# pwr.net
KiCad netlist of a schematic drawn in Altium Designer
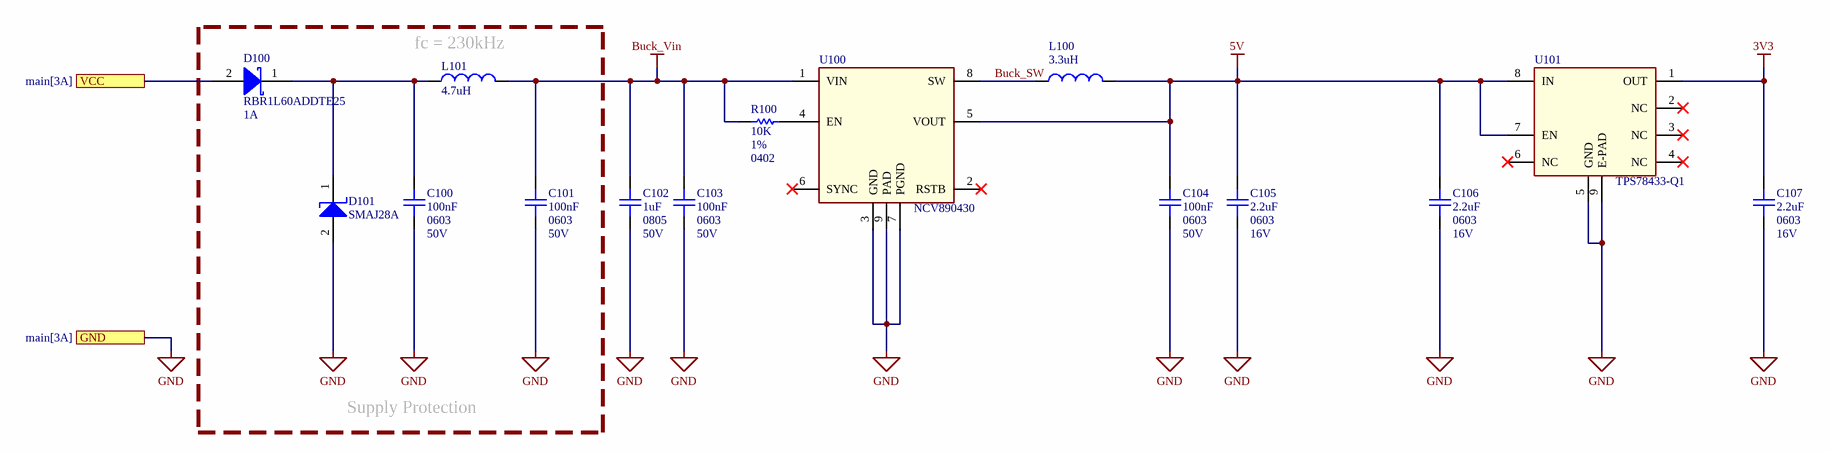
[diagram p0: pwr.SchDoc]

(export (version "E")
  (design (tool "Eeschema 10.0.6"))
  (components
    (comp (ref "C100")
      (value "100nF")
      (footprint "CER0603")
      (description "MLCC Automotive, 100nF, 0603, 50V, 10%, X8L")
      (fields
        (field (name "CASE/PACKAGE") "0603")
        (field (name "OP VOLTAGE") "50V")
        (field (name "TOLERANCE") "10%")
      )
      (libsource (lib "PMP_CapsDB") (part "CapCer_SMD_2"))
    )
    (comp (ref "C101")
      (value "100nF")
      (footprint "CER0603")
      (description "MLCC Automotive, 100nF, 0603, 50V, 10%, X8L")
      (fields
        (field (name "CASE/PACKAGE") "0603")
        (field (name "OP VOLTAGE") "50V")
        (field (name "TOLERANCE") "10%")
      )
      (libsource (lib "PMP_CapsDB") (part "CapCer_SMD_2"))
    )
    (comp (ref "C102")
      (value "1uF")
      (footprint "CER0805")
      (description "MLCC Automotive, 1uF, 0805, 50V, 10%, X7R")
      (fields
        (field (name "CASE/PACKAGE") "0805")
        (field (name "OP VOLTAGE") "50V")
        (field (name "TOLERANCE") "10%")
      )
      (libsource (lib "PMP_CapsDB") (part "CapCer_SMD_2"))
    )
    (comp (ref "C103")
      (value "100nF")
      (footprint "CER0603")
      (description "MLCC Automotive, 100nF, 0603, 50V, 10%, X8L")
      (fields
        (field (name "CASE/PACKAGE") "0603")
        (field (name "OP VOLTAGE") "50V")
        (field (name "TOLERANCE") "10%")
      )
      (libsource (lib "PMP_CapsDB") (part "CapCer_SMD_2"))
    )
    (comp (ref "C104")
      (value "100nF")
      (footprint "CER0603")
      (description "MLCC Automotive, 100nF, 0603, 50V, 10%, X8L")
      (fields
        (field (name "CASE/PACKAGE") "0603")
        (field (name "OP VOLTAGE") "50V")
        (field (name "TOLERANCE") "10%")
      )
      (libsource (lib "PMP_CapsDB") (part "CapCer_SMD_2"))
    )
    (comp (ref "C105")
      (value "2.2uF")
      (footprint "CER0603")
      (description "MLCC Automotive, 2.2uF, 0603, 16V, 10%, X7S")
      (fields
        (field (name "CASE/PACKAGE") "0603")
        (field (name "OP VOLTAGE") "16V")
        (field (name "TOLERANCE") "10%")
      )
      (libsource (lib "PMP_CapsDB") (part "CapCer_SMD_2"))
    )
    (comp (ref "C106")
      (value "2.2uF")
      (footprint "CER0603")
      (description "MLCC Automotive, 2.2uF, 0603, 16V, 10%, X7S")
      (fields
        (field (name "CASE/PACKAGE") "0603")
        (field (name "OP VOLTAGE") "16V")
        (field (name "TOLERANCE") "10%")
      )
      (libsource (lib "PMP_CapsDB") (part "CapCer_SMD_2"))
    )
    (comp (ref "C107")
      (value "2.2uF")
      (footprint "CER0603")
      (description "MLCC Automotive, 2.2uF, 0603, 16V, 10%, X7S")
      (fields
        (field (name "CASE/PACKAGE") "0603")
        (field (name "OP VOLTAGE") "16V")
        (field (name "TOLERANCE") "10%")
      )
      (libsource (lib "PMP_CapsDB") (part "CapCer_SMD_2"))
    )
    (comp (ref "D100")
      (value "RBR1L60ADDTE25")
      (footprint "DO-214AC_SMA")
      (description "Schottky Rectifier Diode 1A 60V SMA")
      (fields (field (name "IF (A)") "1A") (field (name "Comment") "Shottky Rect Diode SMD"))
      (libsource (lib "Pmp_DiscretesDB") (part "Diode_SMD_2_Schottky"))
    )
    (comp (ref "D101")
      (value "SMAJ28A")
      (footprint "DO-214AC_SMA")
      (description "TVS Unidir 28V SMA")
      (fields (field (name "Comment") "SMD/PTH TVS Unidirectional Diode"))
      (libsource (lib "Pmp_DiscretesDB") (part "TVS_2_Unidirectional"))
    )
    (comp (ref "L100")
      (value "3.3uH")
      (footprint "WE-MAPI_1212")
      (description "Power Inductors - SMD WE-MAPI 3,3uH 1.1A DCR=266mOhms AECQ200")
      (fields (field (name "Comment") "SMD Inductor"))
      (libsource (lib "PMP_MagneticsDB") (part "Ind_SMD_2"))
    )
    (comp (ref "L101")
      (value "4.7uH")
      (footprint "WE-LQ_1210")
      (description "EMI Filtering Inductor WE-LQ SMT, 4.7uH, 490mA,")
      (fields (field (name "Comment") "SMD Inductor"))
      (libsource (lib "PMP_MagneticsDB") (part "Ind_SMD_2"))
    )
    (comp (ref "R100")
      (value "10K")
      (footprint "Res0402")
      (description "Thick Film SM Chip Resistors, 10K, 0402, ±1%, 1/10W")
      (fields
        (field (name "TOLERANCE") "1%")
        (field (name "CASE/PACKAGE") "0402")
        (field (name "POWER") "63mW")
        (field (name "Comment") "SMD Resistor")
      )
      (libsource (lib "PMP_ResDB") (part "Res_SMD_2"))
    )
    (comp (ref "U100")
      (value "NCV890430")
      (footprint "SON65P300X300X100-9N")
      (description "synchronous buck converter; 3.5-37Vin; 5Vout; 600mA")
      (fields (field (name "Comment") "ONSEMI_NCV890430"))
      (libsource (lib "PMP_ICsDB") (part "ONSEMI_NCV890430"))
    )
    (comp (ref "U101")
      (value "TPS78433-Q1")
      (footprint "SON65P300X100_HS-9N")
      (description "TPS784-Q1 Automotive, 3.3V, 300mA, High-PSRR LDO")
      (fields (field (name "Comment") "TI_TPS78533Q_VSON"))
      (libsource (lib "PMP_ICsDB") (part "TI_TPS78533Q_VSON"))
    )
  )
  (nets
    (net (code "1") (name "/Buck_SW") (class "Default")
      (node (ref "L100") (pin "1") (pinfunction "1_1") (pintype "passive"))
      (node (ref "U100") (pin "8") (pinfunction "SW_8") (pintype "passive"))
    )
    (net (code "2") (name "/VCC") (class "Default")
      (node (ref "D100") (pin "2") (pinfunction "A_2") (pintype "passive"))
    )
    (net (code "3") (name "3V3") (class "Default")
      (node (ref "C107") (pin "1") (pinfunction "1_1") (pintype "passive"))
      (node (ref "U101") (pin "1") (pinfunction "OUT_1") (pintype "power_in"))
    )
    (net (code "4") (name "5V") (class "Default")
      (node (ref "C104") (pin "1") (pinfunction "1_1") (pintype "passive"))
      (node (ref "C105") (pin "1") (pinfunction "1_1") (pintype "passive"))
      (node (ref "C106") (pin "1") (pinfunction "1_1") (pintype "passive"))
      (node (ref "L100") (pin "2") (pinfunction "2_2") (pintype "passive"))
      (node (ref "U100") (pin "5") (pinfunction "VOUT_5") (pintype "passive"))
      (node (ref "U101") (pin "7") (pinfunction "EN_7") (pintype "passive"))
      (node (ref "U101") (pin "8") (pinfunction "IN_8") (pintype "power_in"))
    )
    (net (code "5") (name "Buck_Vin") (class "Default")
      (node (ref "C101") (pin "1") (pinfunction "1_1") (pintype "passive"))
      (node (ref "C102") (pin "1") (pinfunction "1_1") (pintype "passive"))
      (node (ref "C103") (pin "1") (pinfunction "1_1") (pintype "passive"))
      (node (ref "L101") (pin "2") (pinfunction "2_2") (pintype "passive"))
      (node (ref "R100") (pin "2") (pinfunction "2_2") (pintype "passive"))
      (node (ref "U100") (pin "1") (pinfunction "VIN_1") (pintype "passive"))
    )
    (net (code "6") (name "GND") (class "Default")
      (node (ref "C100") (pin "2") (pinfunction "2_2") (pintype "passive"))
      (node (ref "C101") (pin "2") (pinfunction "2_2") (pintype "passive"))
      (node (ref "C102") (pin "2") (pinfunction "2_2") (pintype "passive"))
      (node (ref "C103") (pin "2") (pinfunction "2_2") (pintype "passive"))
      (node (ref "C104") (pin "2") (pinfunction "2_2") (pintype "passive"))
      (node (ref "C105") (pin "2") (pinfunction "2_2") (pintype "passive"))
      (node (ref "C106") (pin "2") (pinfunction "2_2") (pintype "passive"))
      (node (ref "C107") (pin "2") (pinfunction "2_2") (pintype "passive"))
      (node (ref "D101") (pin "2") (pinfunction "A_2") (pintype "passive"))
      (node (ref "U100") (pin "3") (pinfunction "GND_3") (pintype "passive"))
      (node (ref "U100") (pin "7") (pinfunction "PGND_7") (pintype "passive"))
      (node (ref "U100") (pin "9") (pinfunction "PAD_9") (pintype "passive"))
      (node (ref "U101") (pin "5") (pinfunction "GND_5") (pintype "power_in"))
      (node (ref "U101") (pin "9") (pinfunction "E-PAD_9") (pintype "passive"))
    )
    (net (code "7") (name "Net-(D100-K)") (class "Default")
      (node (ref "C100") (pin "1") (pinfunction "1_1") (pintype "passive"))
      (node (ref "D100") (pin "1") (pinfunction "K_1") (pintype "passive"))
      (node (ref "D101") (pin "1") (pinfunction "K_1") (pintype "passive"))
      (node (ref "L101") (pin "1") (pinfunction "1_1") (pintype "passive"))
    )
    (net (code "8") (name "Net-(U100-EN)") (class "Default")
      (node (ref "R100") (pin "1") (pinfunction "1_1") (pintype "passive"))
      (node (ref "U100") (pin "4") (pinfunction "EN_4") (pintype "passive"))
    )
    (net (code "9") (name "unconnected-(U100-RSTB-Pad2)") (class "Default")
      (node (ref "U100") (pin "2") (pinfunction "RSTB_2") (pintype "passive+no_connect"))
    )
    (net (code "10") (name "unconnected-(U100-SYNC-Pad6)") (class "Default")
      (node (ref "U100") (pin "6") (pinfunction "SYNC_6") (pintype "passive+no_connect"))
    )
    (net (code "11") (name "unconnected-(U101-NC-Pad2)") (class "Default")
      (node (ref "U101") (pin "2") (pinfunction "NC_2") (pintype "passive+no_connect"))
    )
    (net (code "12") (name "unconnected-(U101-NC-Pad3)") (class "Default")
      (node (ref "U101") (pin "3") (pinfunction "NC_3") (pintype "passive+no_connect"))
    )
    (net (code "13") (name "unconnected-(U101-NC-Pad4)") (class "Default")
      (node (ref "U101") (pin "4") (pinfunction "NC_4") (pintype "passive+no_connect"))
    )
    (net (code "14") (name "unconnected-(U101-NC-Pad6)") (class "Default")
      (node (ref "U101") (pin "6") (pinfunction "NC_6") (pintype "passive+no_connect"))
    )
  )
)
